# ByteBlaster.net
KiCad netlist of a schematic drawn in EAGLE
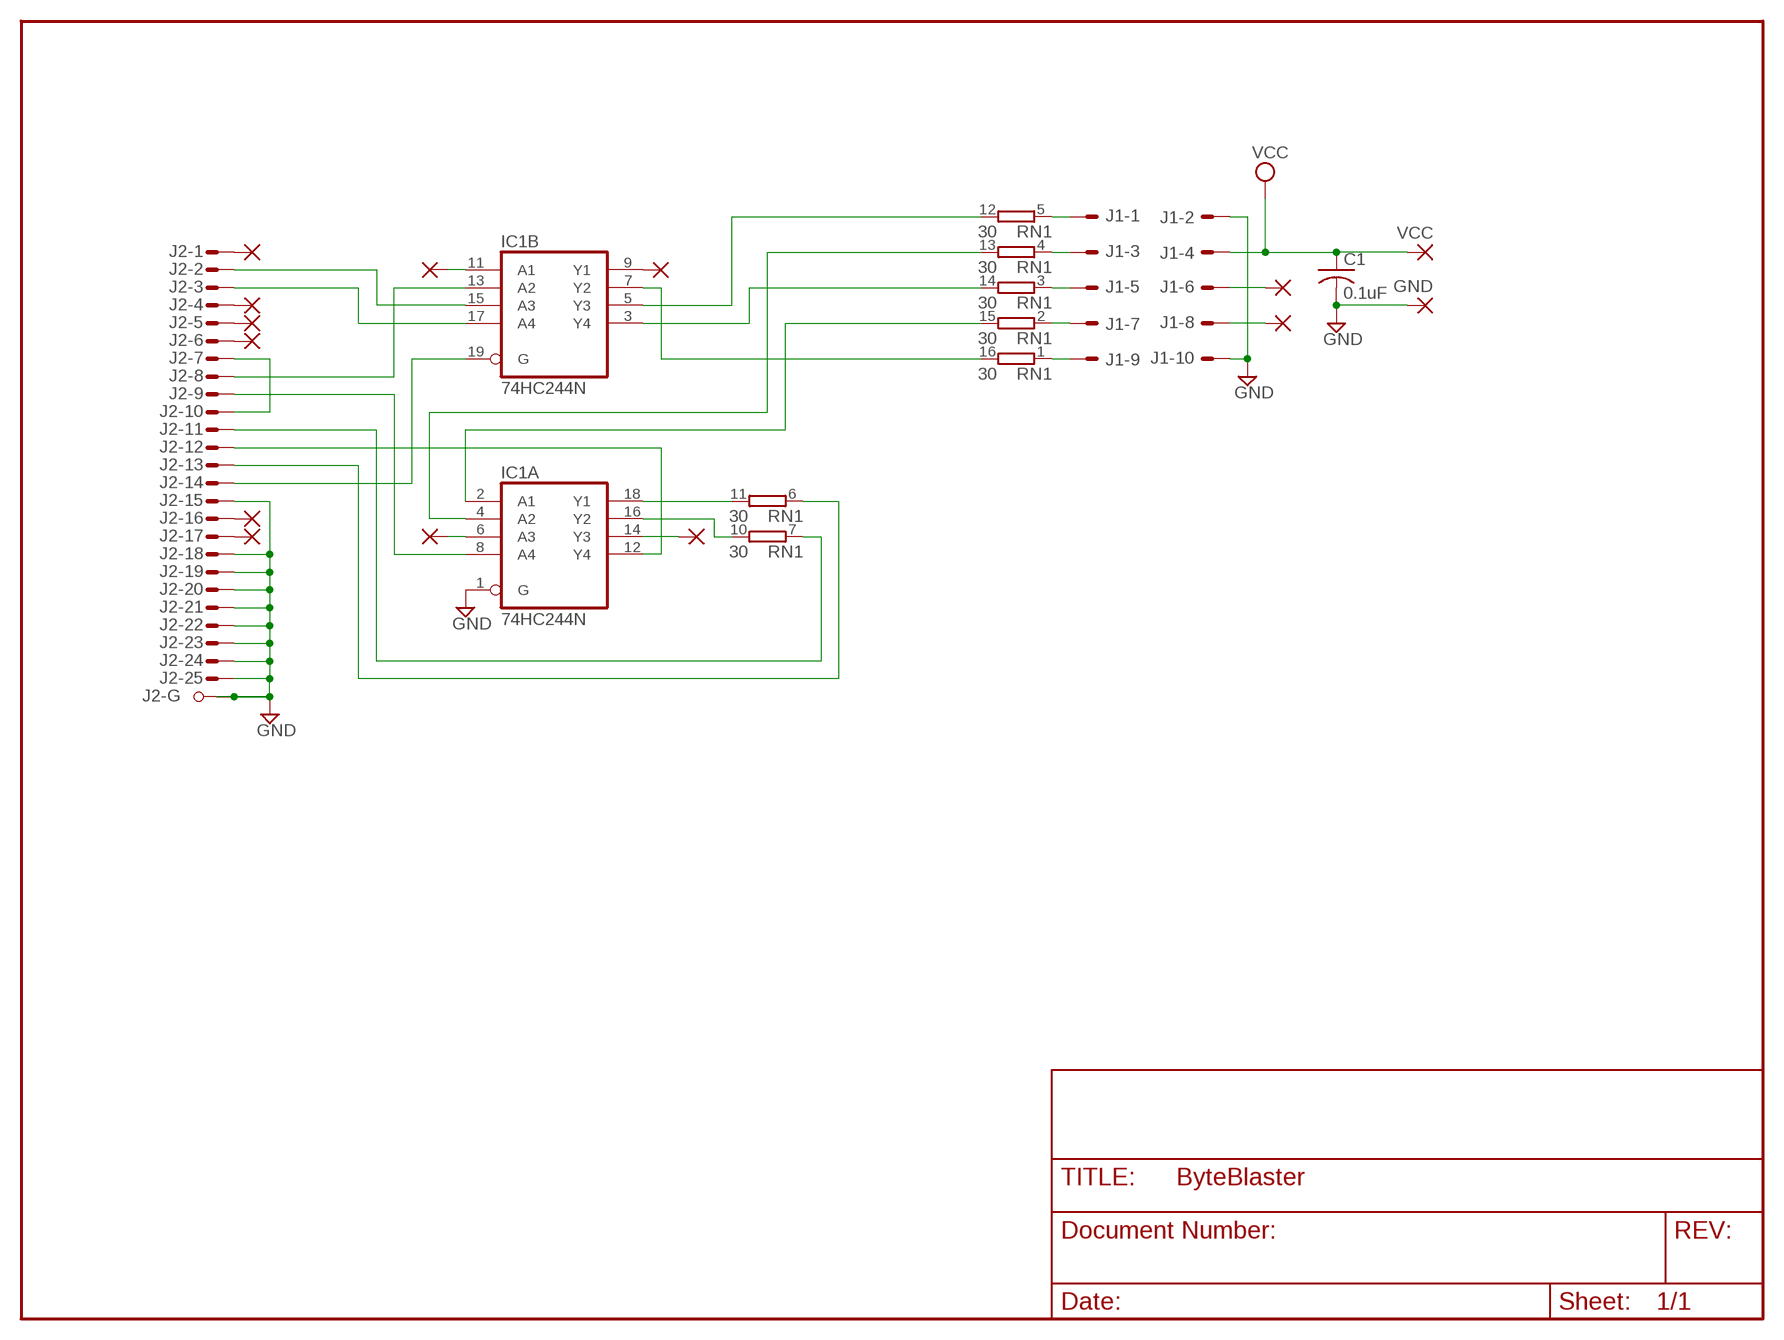
[diagram p0: schematic, sheet 1]

(export (version "E")
  (design (tool "Eeschema 10.0.6"))
  (components
    (comp (ref "C1")
      (value "0.1uF")
      (footprint "eagle-import:C050-025X075")
      (libsource (lib "eagle-import") (part "C-US050-025X075"))
    )
    (comp (ref "GND")
      (value "1,6/0,9")
      (footprint "eagle-import:1,6_0,9")
      (libsource (lib "eagle-import") (part "1,6/0,9"))
    )
    (comp (ref "IC1")
      (value "74HC244N")
      (footprint "eagle-import:DIL20")
      (libsource (lib "eagle-import") (part "74244NHC"))
    )
    (comp (ref "J1")
      (value "ML10E")
      (footprint "eagle-import:ML10")
      (libsource (lib "eagle-import") (part "ML10?E"))
    )
    (comp (ref "J2")
      (value "M25VPS")
      (footprint "eagle-import:M25VP")
      (libsource (lib "eagle-import") (part "M25VPS"))
    )
    (comp (ref "PAD1")
      (value "1,6/0,9")
      (footprint "eagle-import:1,6_0,9")
      (libsource (lib "eagle-import") (part "1,6/0,9"))
    )
    (comp (ref "PAD2")
      (value "1,6/0,9")
      (footprint "eagle-import:1,6_0,9")
      (libsource (lib "eagle-import") (part "1,6/0,9"))
    )
    (comp (ref "PAD3")
      (value "1,6/0,9")
      (footprint "eagle-import:1,6_0,9")
      (libsource (lib "eagle-import") (part "1,6/0,9"))
    )
    (comp (ref "PAD4")
      (value "1,6/0,9")
      (footprint "eagle-import:1,6_0,9")
      (libsource (lib "eagle-import") (part "1,6/0,9"))
    )
    (comp (ref "PAD5")
      (value "1,6/0,9")
      (footprint "eagle-import:1,6_0,9")
      (libsource (lib "eagle-import") (part "1,6/0,9"))
    )
    (comp (ref "PAD6")
      (value "1,6/0,9")
      (footprint "eagle-import:1,6_0,9")
      (libsource (lib "eagle-import") (part "1,6/0,9"))
    )
    (comp (ref "PAD7")
      (value "1,6/0,9")
      (footprint "eagle-import:1,6_0,9")
      (libsource (lib "eagle-import") (part "1,6/0,9"))
    )
    (comp (ref "PAD8")
      (value "1,6/0,9")
      (footprint "eagle-import:1,6_0,9")
      (libsource (lib "eagle-import") (part "1,6/0,9"))
    )
    (comp (ref "PAD9")
      (value "1,6/0,9")
      (footprint "eagle-import:1,6_0,9")
      (libsource (lib "eagle-import") (part "1,6/0,9"))
    )
    (comp (ref "PAD10")
      (value "1,6/0,9")
      (footprint "eagle-import:1,6_0,9")
      (libsource (lib "eagle-import") (part "1,6/0,9"))
    )
    (comp (ref "PAD11")
      (value "1,6/0,9")
      (footprint "eagle-import:1,6_0,9")
      (libsource (lib "eagle-import") (part "1,6/0,9"))
    )
    (comp (ref "PAD12")
      (value "1,6/0,9")
      (footprint "eagle-import:1,6_0,9")
      (libsource (lib "eagle-import") (part "1,6/0,9"))
    )
    (comp (ref "RN1")
      (value "30")
      (footprint "eagle-import:DIL16")
      (libsource (lib "eagle-import") (part "8R-P"))
    )
    (comp (ref "VCC")
      (value "1,6/0,9")
      (footprint "eagle-import:1,6_0,9")
      (libsource (lib "eagle-import") (part "1,6/0,9"))
    )
  )
  (nets
    (net (code "1") (name "GND") (class "Default")
      (node (ref "C1") (pin "2") (pinfunction "2_2") (pintype "passive"))
      (node (ref "GND") (pin "1") (pinfunction "P_1") (pintype "passive"))
      (node (ref "IC1") (pin "1") (pinfunction "G_1") (pintype "input"))
      (node (ref "J1") (pin "10") (pinfunction "S_10") (pintype "passive"))
      (node (ref "J1") (pin "2") (pinfunction "S_2") (pintype "passive"))
      (node (ref "J2") (pin "15") (pinfunction "M_15") (pintype "passive"))
      (node (ref "J2") (pin "18") (pinfunction "M_18") (pintype "passive"))
      (node (ref "J2") (pin "19") (pinfunction "M_19") (pintype "passive"))
      (node (ref "J2") (pin "20") (pinfunction "M_20") (pintype "passive"))
      (node (ref "J2") (pin "21") (pinfunction "M_21") (pintype "passive"))
      (node (ref "J2") (pin "22") (pinfunction "M_22") (pintype "passive"))
      (node (ref "J2") (pin "23") (pinfunction "M_23") (pintype "passive"))
      (node (ref "J2") (pin "24") (pinfunction "M_24") (pintype "passive"))
      (node (ref "J2") (pin "25") (pinfunction "M_25") (pintype "passive"))
      (node (ref "J2") (pin "G1") (pinfunction "G1_G1") (pintype "passive"))
      (node (ref "J2") (pin "G2") (pinfunction "G2_G2") (pintype "passive"))
    )
    (net (code "2") (name "Net-(IC1A-A1)") (class "Default")
      (node (ref "IC1") (pin "2") (pinfunction "A1_2") (pintype "input"))
      (node (ref "RN1") (pin "15") (pinfunction "2_15") (pintype "passive"))
    )
    (net (code "3") (name "Net-(IC1A-A2)") (class "Default")
      (node (ref "IC1") (pin "4") (pinfunction "A2_4") (pintype "input"))
      (node (ref "RN1") (pin "13") (pinfunction "2_13") (pintype "passive"))
    )
    (net (code "4") (name "Net-(IC1A-A3)") (class "Default")
      (node (ref "IC1") (pin "6") (pinfunction "A3_6") (pintype "input"))
      (node (ref "PAD8") (pin "1") (pinfunction "P_1") (pintype "passive"))
    )
    (net (code "5") (name "Net-(IC1A-A4)") (class "Default")
      (node (ref "IC1") (pin "8") (pinfunction "A4_8") (pintype "input"))
      (node (ref "J2") (pin "9") (pinfunction "M_9") (pintype "passive"))
    )
    (net (code "6") (name "Net-(IC1A-Y1)") (class "Default")
      (node (ref "IC1") (pin "18") (pinfunction "Y1_18") (pintype "tri_state"))
      (node (ref "RN1") (pin "11") (pinfunction "2_11") (pintype "passive"))
    )
    (net (code "7") (name "Net-(IC1A-Y2)") (class "Default")
      (node (ref "IC1") (pin "16") (pinfunction "Y2_16") (pintype "tri_state"))
      (node (ref "RN1") (pin "10") (pinfunction "2_10") (pintype "passive"))
    )
    (net (code "8") (name "Net-(IC1A-Y3)") (class "Default")
      (node (ref "IC1") (pin "14") (pinfunction "Y3_14") (pintype "tri_state"))
      (node (ref "PAD12") (pin "1") (pinfunction "P_1") (pintype "passive"))
    )
    (net (code "9") (name "Net-(IC1A-Y4)") (class "Default")
      (node (ref "IC1") (pin "12") (pinfunction "Y4_12") (pintype "tri_state"))
      (node (ref "J2") (pin "12") (pinfunction "M_12") (pintype "passive"))
    )
    (net (code "10") (name "Net-(IC1B-A1)") (class "Default")
      (node (ref "IC1") (pin "11") (pinfunction "A1_11") (pintype "input"))
      (node (ref "PAD7") (pin "1") (pinfunction "P_1") (pintype "passive"))
    )
    (net (code "11") (name "Net-(IC1B-A2)") (class "Default")
      (node (ref "IC1") (pin "13") (pinfunction "A2_13") (pintype "input"))
      (node (ref "J2") (pin "8") (pinfunction "M_8") (pintype "passive"))
    )
    (net (code "12") (name "Net-(IC1B-A3)") (class "Default")
      (node (ref "IC1") (pin "15") (pinfunction "A3_15") (pintype "input"))
      (node (ref "J2") (pin "2") (pinfunction "M_2") (pintype "passive"))
    )
    (net (code "13") (name "Net-(IC1B-A4)") (class "Default")
      (node (ref "IC1") (pin "17") (pinfunction "A4_17") (pintype "input"))
      (node (ref "J2") (pin "3") (pinfunction "M_3") (pintype "passive"))
    )
    (net (code "14") (name "Net-(IC1B-G)") (class "Default")
      (node (ref "IC1") (pin "19") (pinfunction "G_19") (pintype "input"))
      (node (ref "J2") (pin "14") (pinfunction "M_14") (pintype "passive"))
    )
    (net (code "15") (name "Net-(IC1B-Y1)") (class "Default")
      (node (ref "IC1") (pin "9") (pinfunction "Y1_9") (pintype "tri_state"))
      (node (ref "PAD11") (pin "1") (pinfunction "P_1") (pintype "passive"))
    )
    (net (code "16") (name "Net-(IC1B-Y2)") (class "Default")
      (node (ref "IC1") (pin "7") (pinfunction "Y2_7") (pintype "tri_state"))
      (node (ref "RN1") (pin "16") (pinfunction "2_16") (pintype "passive"))
    )
    (net (code "17") (name "Net-(IC1B-Y3)") (class "Default")
      (node (ref "IC1") (pin "5") (pinfunction "Y3_5") (pintype "tri_state"))
      (node (ref "RN1") (pin "12") (pinfunction "2_12") (pintype "passive"))
    )
    (net (code "18") (name "Net-(IC1B-Y4)") (class "Default")
      (node (ref "IC1") (pin "3") (pinfunction "Y4_3") (pintype "tri_state"))
      (node (ref "RN1") (pin "14") (pinfunction "2_14") (pintype "passive"))
    )
    (net (code "19") (name "Net-(J1A-S)") (class "Default")
      (node (ref "J1") (pin "1") (pinfunction "S_1") (pintype "passive"))
      (node (ref "RN1") (pin "5") (pinfunction "1_5") (pintype "passive"))
    )
    (net (code "20") (name "Net-(J1D-S)") (class "Default")
      (node (ref "J1") (pin "3") (pinfunction "S_3") (pintype "passive"))
      (node (ref "RN1") (pin "4") (pinfunction "1_4") (pintype "passive"))
    )
    (net (code "21") (name "Net-(J1F-S)") (class "Default")
      (node (ref "J1") (pin "5") (pinfunction "S_5") (pintype "passive"))
      (node (ref "RN1") (pin "3") (pinfunction "1_3") (pintype "passive"))
    )
    (net (code "22") (name "Net-(J1G-S)") (class "Default")
      (node (ref "J1") (pin "6") (pinfunction "S_6") (pintype "passive"))
      (node (ref "PAD9") (pin "1") (pinfunction "P_1") (pintype "passive"))
    )
    (net (code "23") (name "Net-(J1H-S)") (class "Default")
      (node (ref "J1") (pin "7") (pinfunction "S_7") (pintype "passive"))
      (node (ref "RN1") (pin "2") (pinfunction "1_2") (pintype "passive"))
    )
    (net (code "24") (name "Net-(J1I-S)") (class "Default")
      (node (ref "J1") (pin "8") (pinfunction "S_8") (pintype "passive"))
      (node (ref "PAD10") (pin "1") (pinfunction "P_1") (pintype "passive"))
    )
    (net (code "25") (name "Net-(J1J-S)") (class "Default")
      (node (ref "J1") (pin "9") (pinfunction "S_9") (pintype "passive"))
      (node (ref "RN1") (pin "1") (pinfunction "1_1") (pintype "passive"))
    )
    (net (code "26") (name "Net-(J2A-M)") (class "Default")
      (node (ref "J2") (pin "1") (pinfunction "M_1") (pintype "passive"))
      (node (ref "PAD1") (pin "1") (pinfunction "P_1") (pintype "passive"))
    )
    (net (code "27") (name "Net-(J2B-M)") (class "Default")
      (node (ref "J2") (pin "10") (pinfunction "M_10") (pintype "passive"))
      (node (ref "J2") (pin "7") (pinfunction "M_7") (pintype "passive"))
    )
    (net (code "28") (name "Net-(J2C-M)") (class "Default")
      (node (ref "J2") (pin "11") (pinfunction "M_11") (pintype "passive"))
      (node (ref "RN1") (pin "7") (pinfunction "1_7") (pintype "passive"))
    )
    (net (code "29") (name "Net-(J2E-M)") (class "Default")
      (node (ref "J2") (pin "13") (pinfunction "M_13") (pintype "passive"))
      (node (ref "RN1") (pin "6") (pinfunction "1_6") (pintype "passive"))
    )
    (net (code "30") (name "Net-(J2H-M)") (class "Default")
      (node (ref "J2") (pin "16") (pinfunction "M_16") (pintype "passive"))
      (node (ref "PAD5") (pin "1") (pinfunction "P_1") (pintype "passive"))
    )
    (net (code "31") (name "Net-(J2I-M)") (class "Default")
      (node (ref "J2") (pin "17") (pinfunction "M_17") (pintype "passive"))
      (node (ref "PAD6") (pin "1") (pinfunction "P_1") (pintype "passive"))
    )
    (net (code "32") (name "Net-(J2T-M)") (class "Default")
      (node (ref "J2") (pin "4") (pinfunction "M_4") (pintype "passive"))
      (node (ref "PAD2") (pin "1") (pinfunction "P_1") (pintype "passive"))
    )
    (net (code "33") (name "Net-(J2U-M)") (class "Default")
      (node (ref "J2") (pin "5") (pinfunction "M_5") (pintype "passive"))
      (node (ref "PAD3") (pin "1") (pinfunction "P_1") (pintype "passive"))
    )
    (net (code "34") (name "Net-(J2V-M)") (class "Default")
      (node (ref "J2") (pin "6") (pinfunction "M_6") (pintype "passive"))
      (node (ref "PAD4") (pin "1") (pinfunction "P_1") (pintype "passive"))
    )
    (net (code "35") (name "VCC") (class "Default")
      (node (ref "C1") (pin "1") (pinfunction "1_1") (pintype "passive"))
      (node (ref "J1") (pin "4") (pinfunction "S_4") (pintype "passive"))
      (node (ref "VCC") (pin "1") (pinfunction "P_1") (pintype "passive"))
    )
  )
)
